# ADF_Copy_v0_5.net
KiCad netlist of a schematic drawn in EAGLE
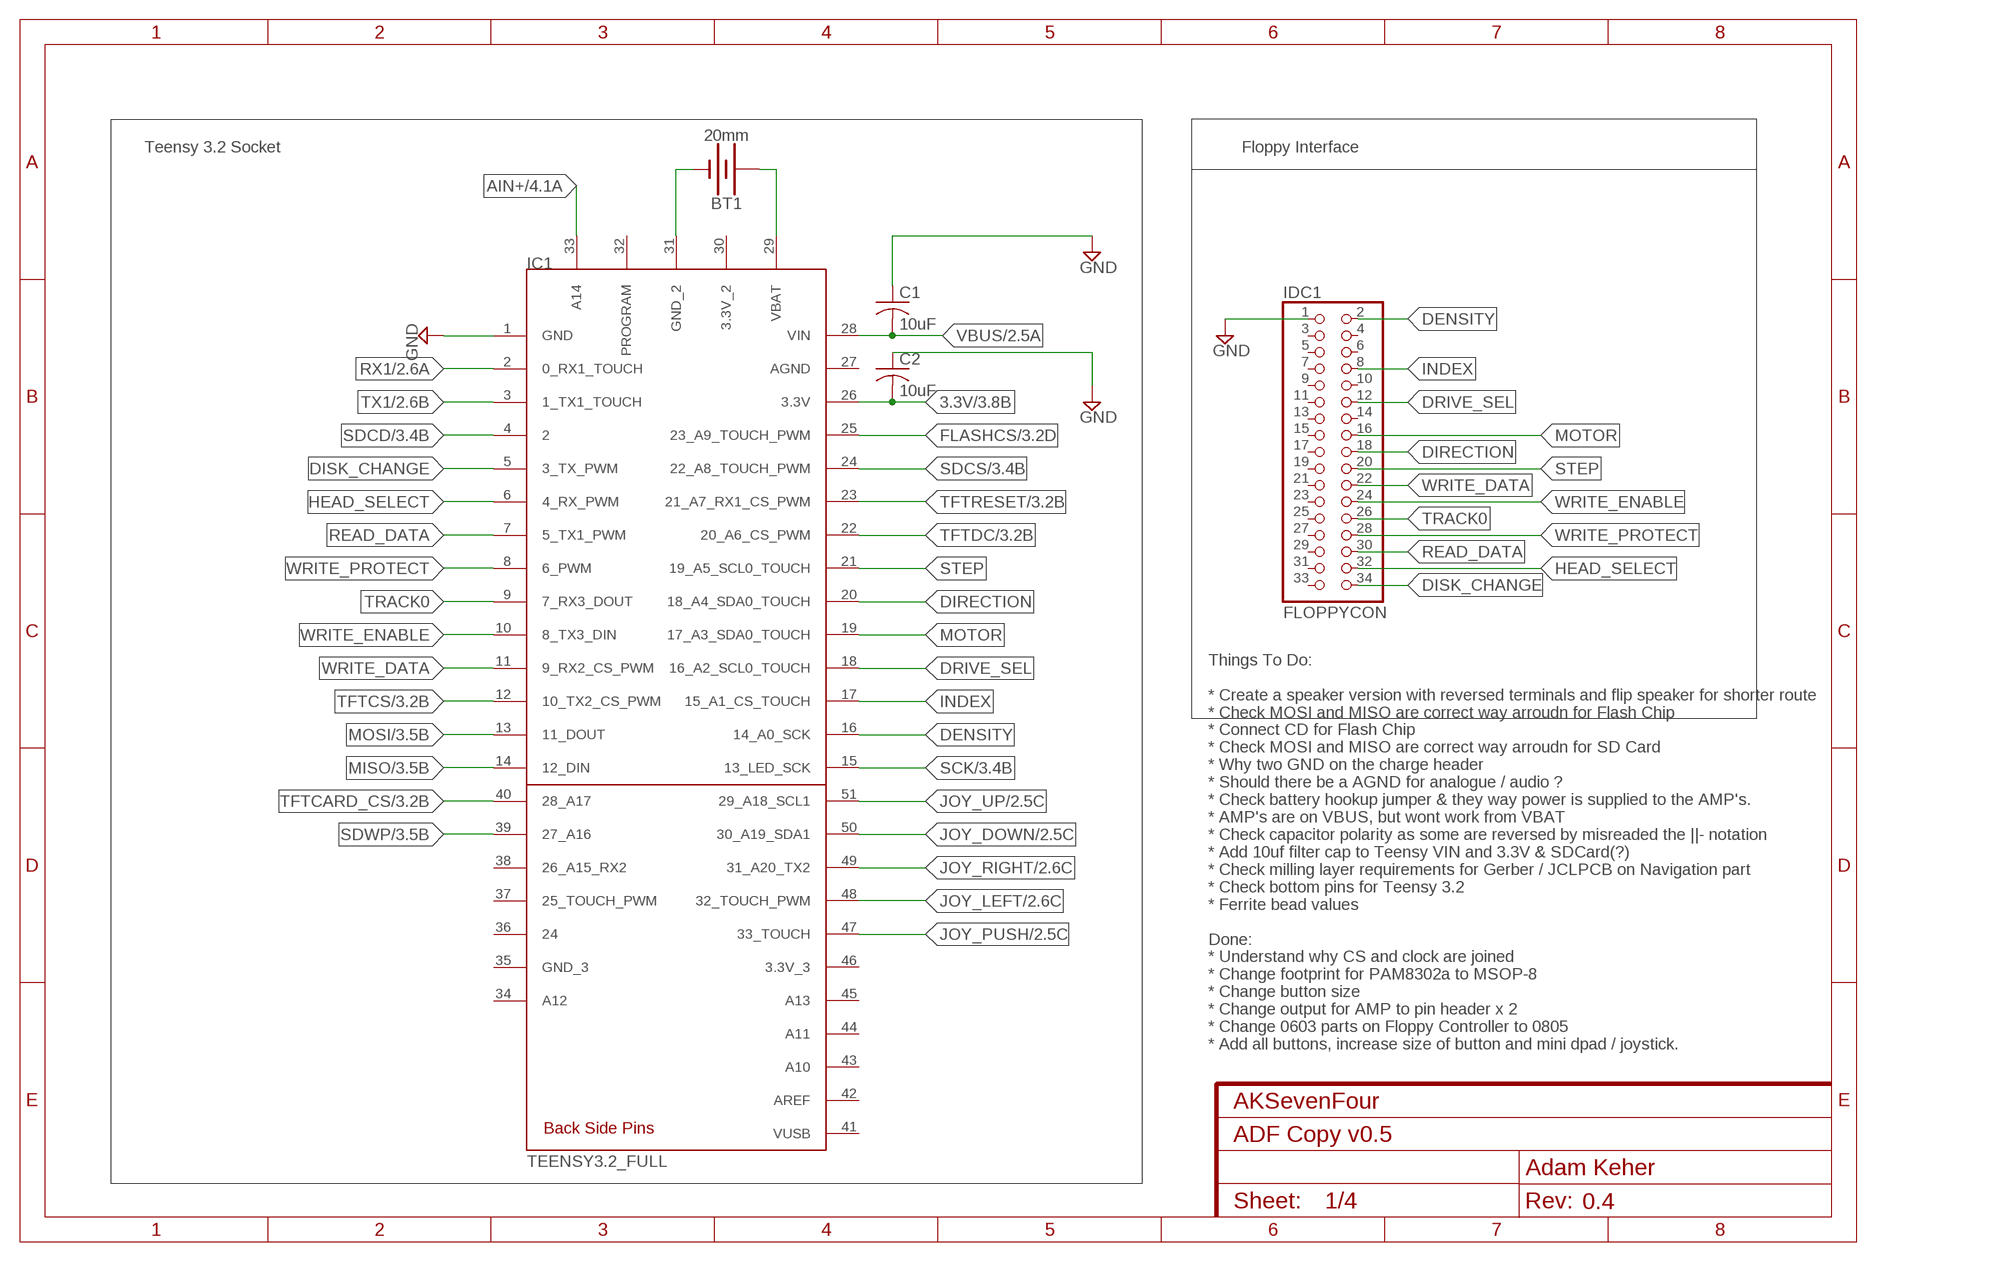
[diagram p0: schematic, sheet 1]
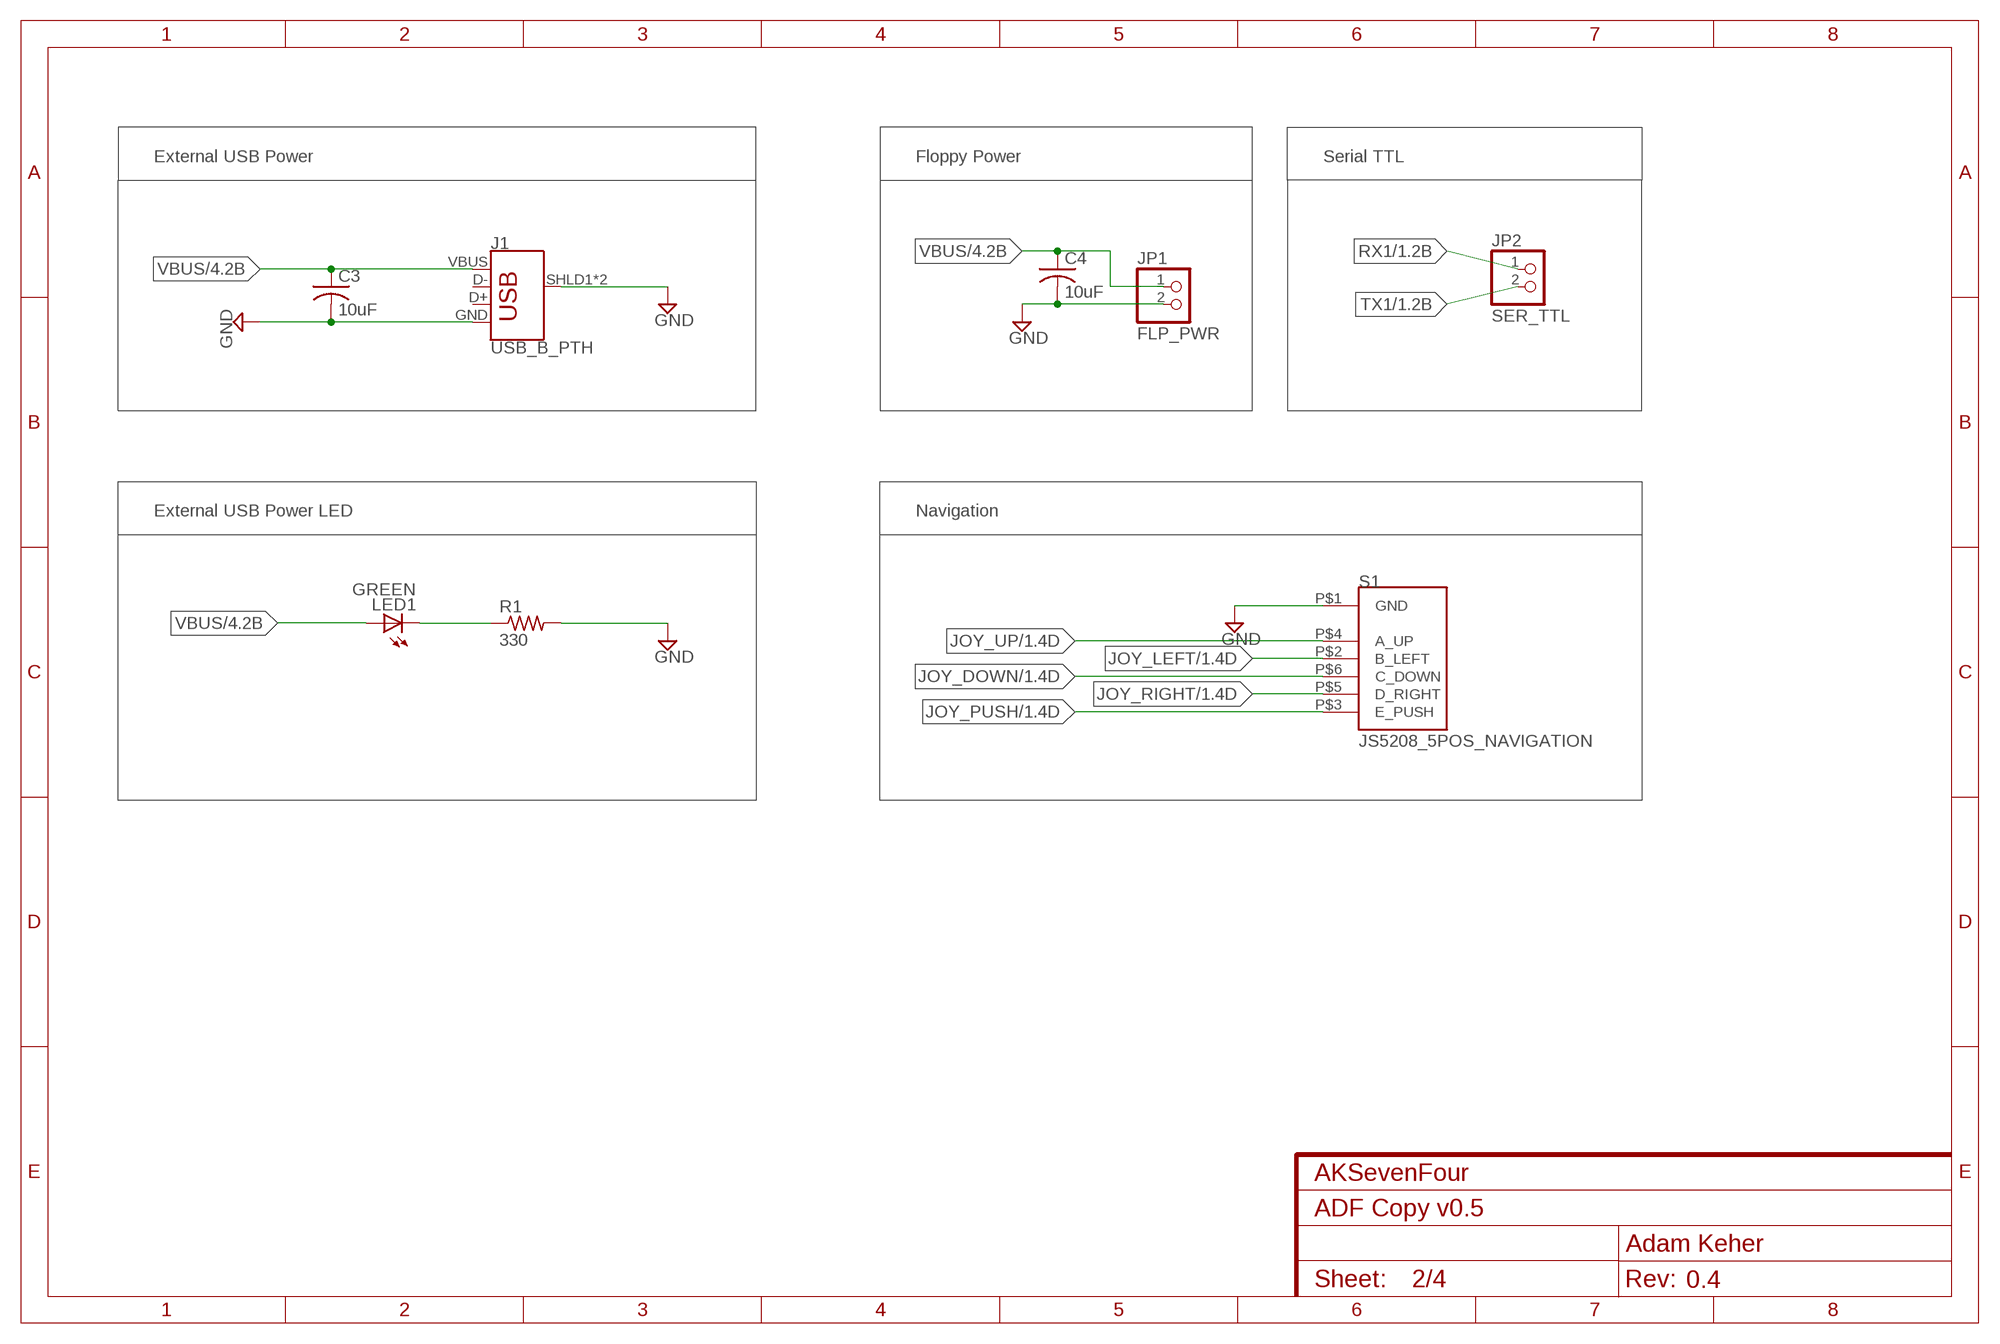
[diagram p1: schematic, sheet 2]
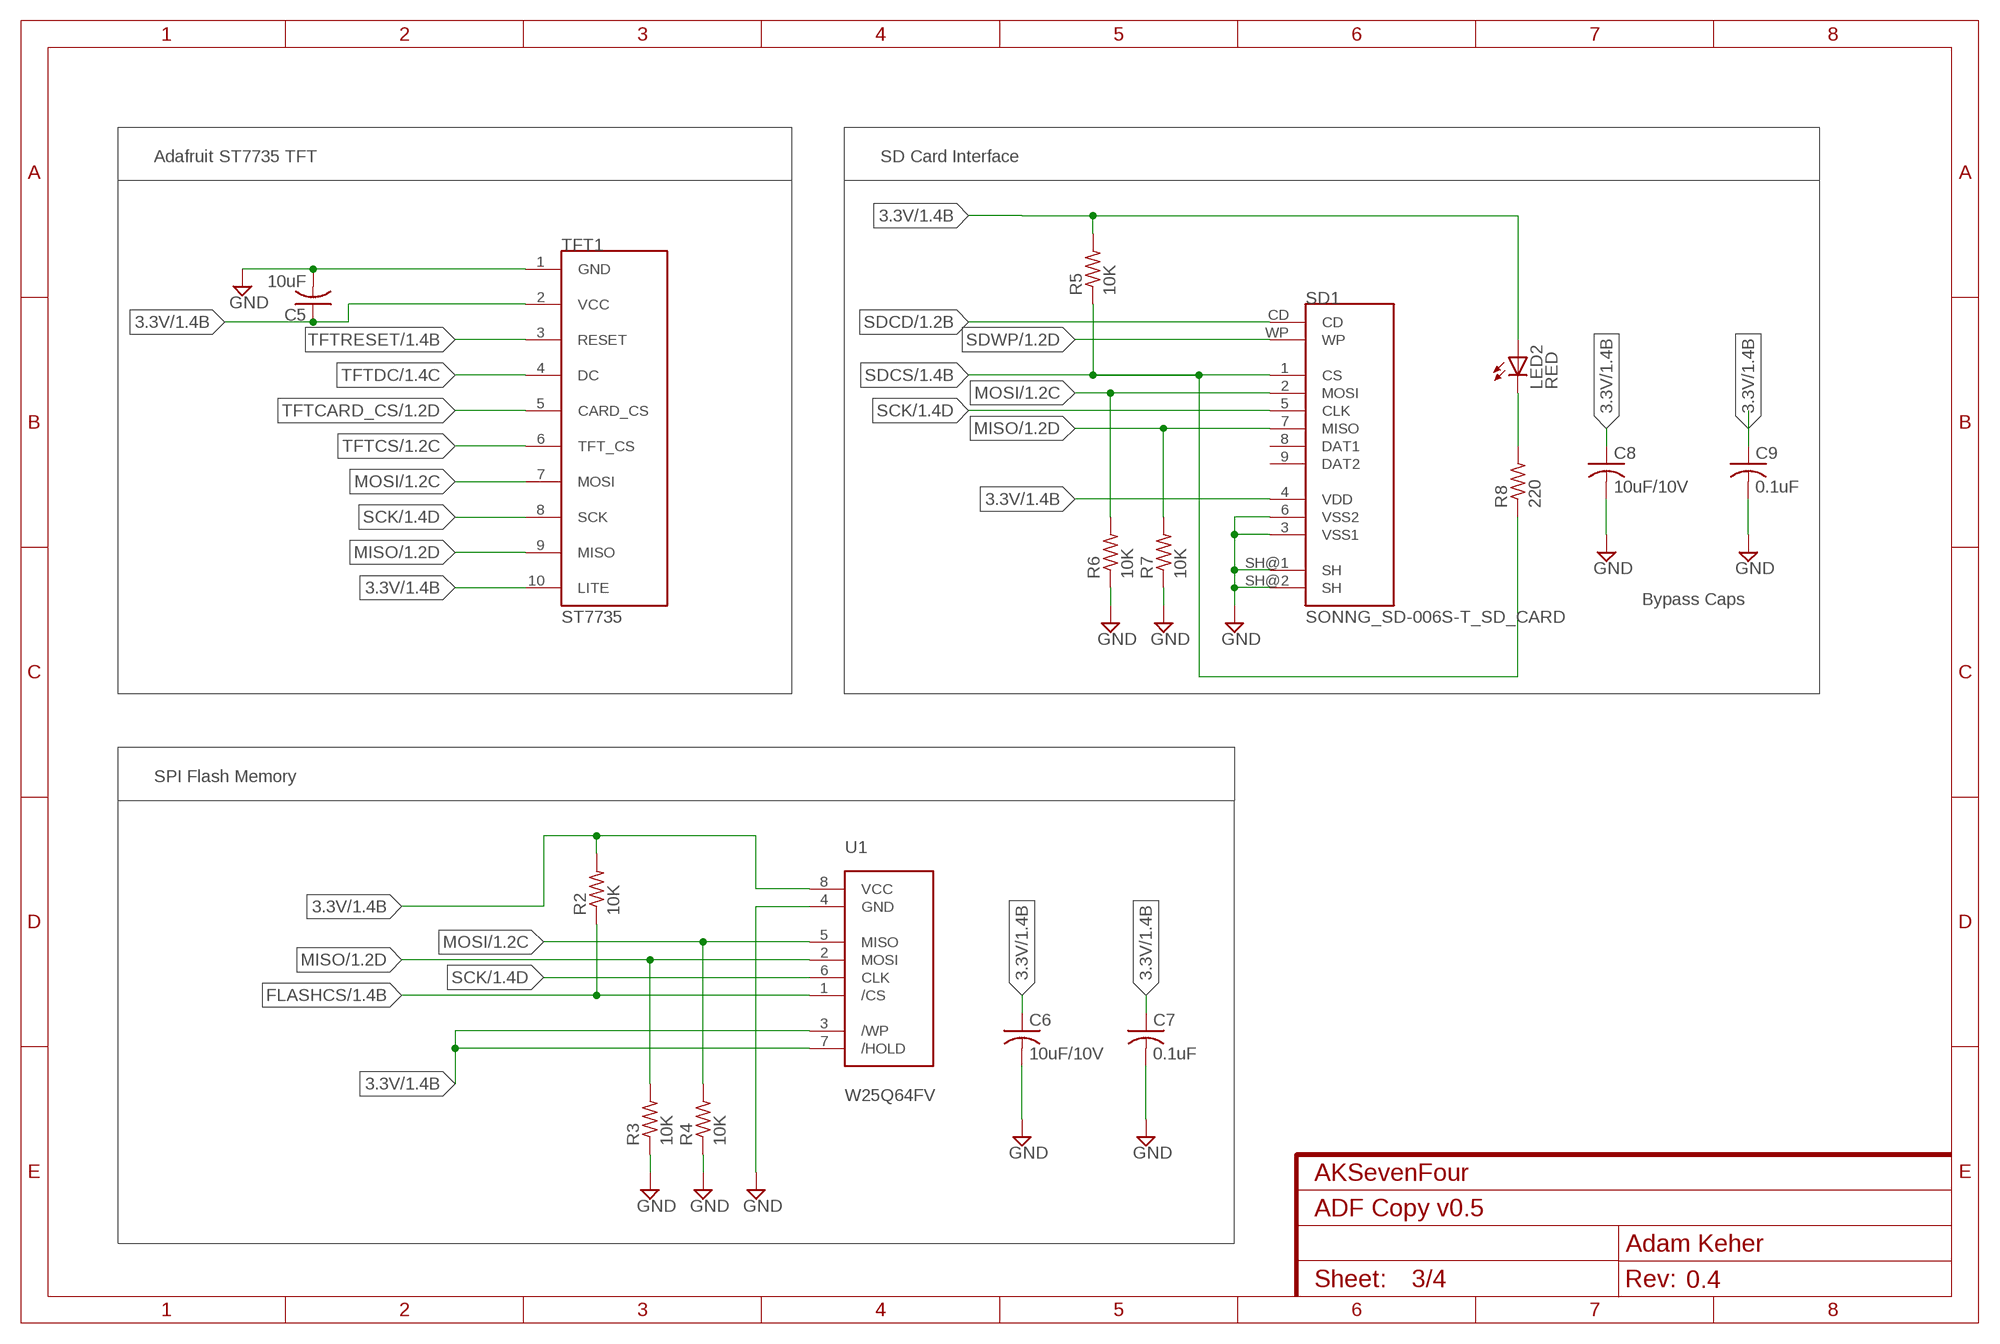
[diagram p2: schematic, sheet 3]
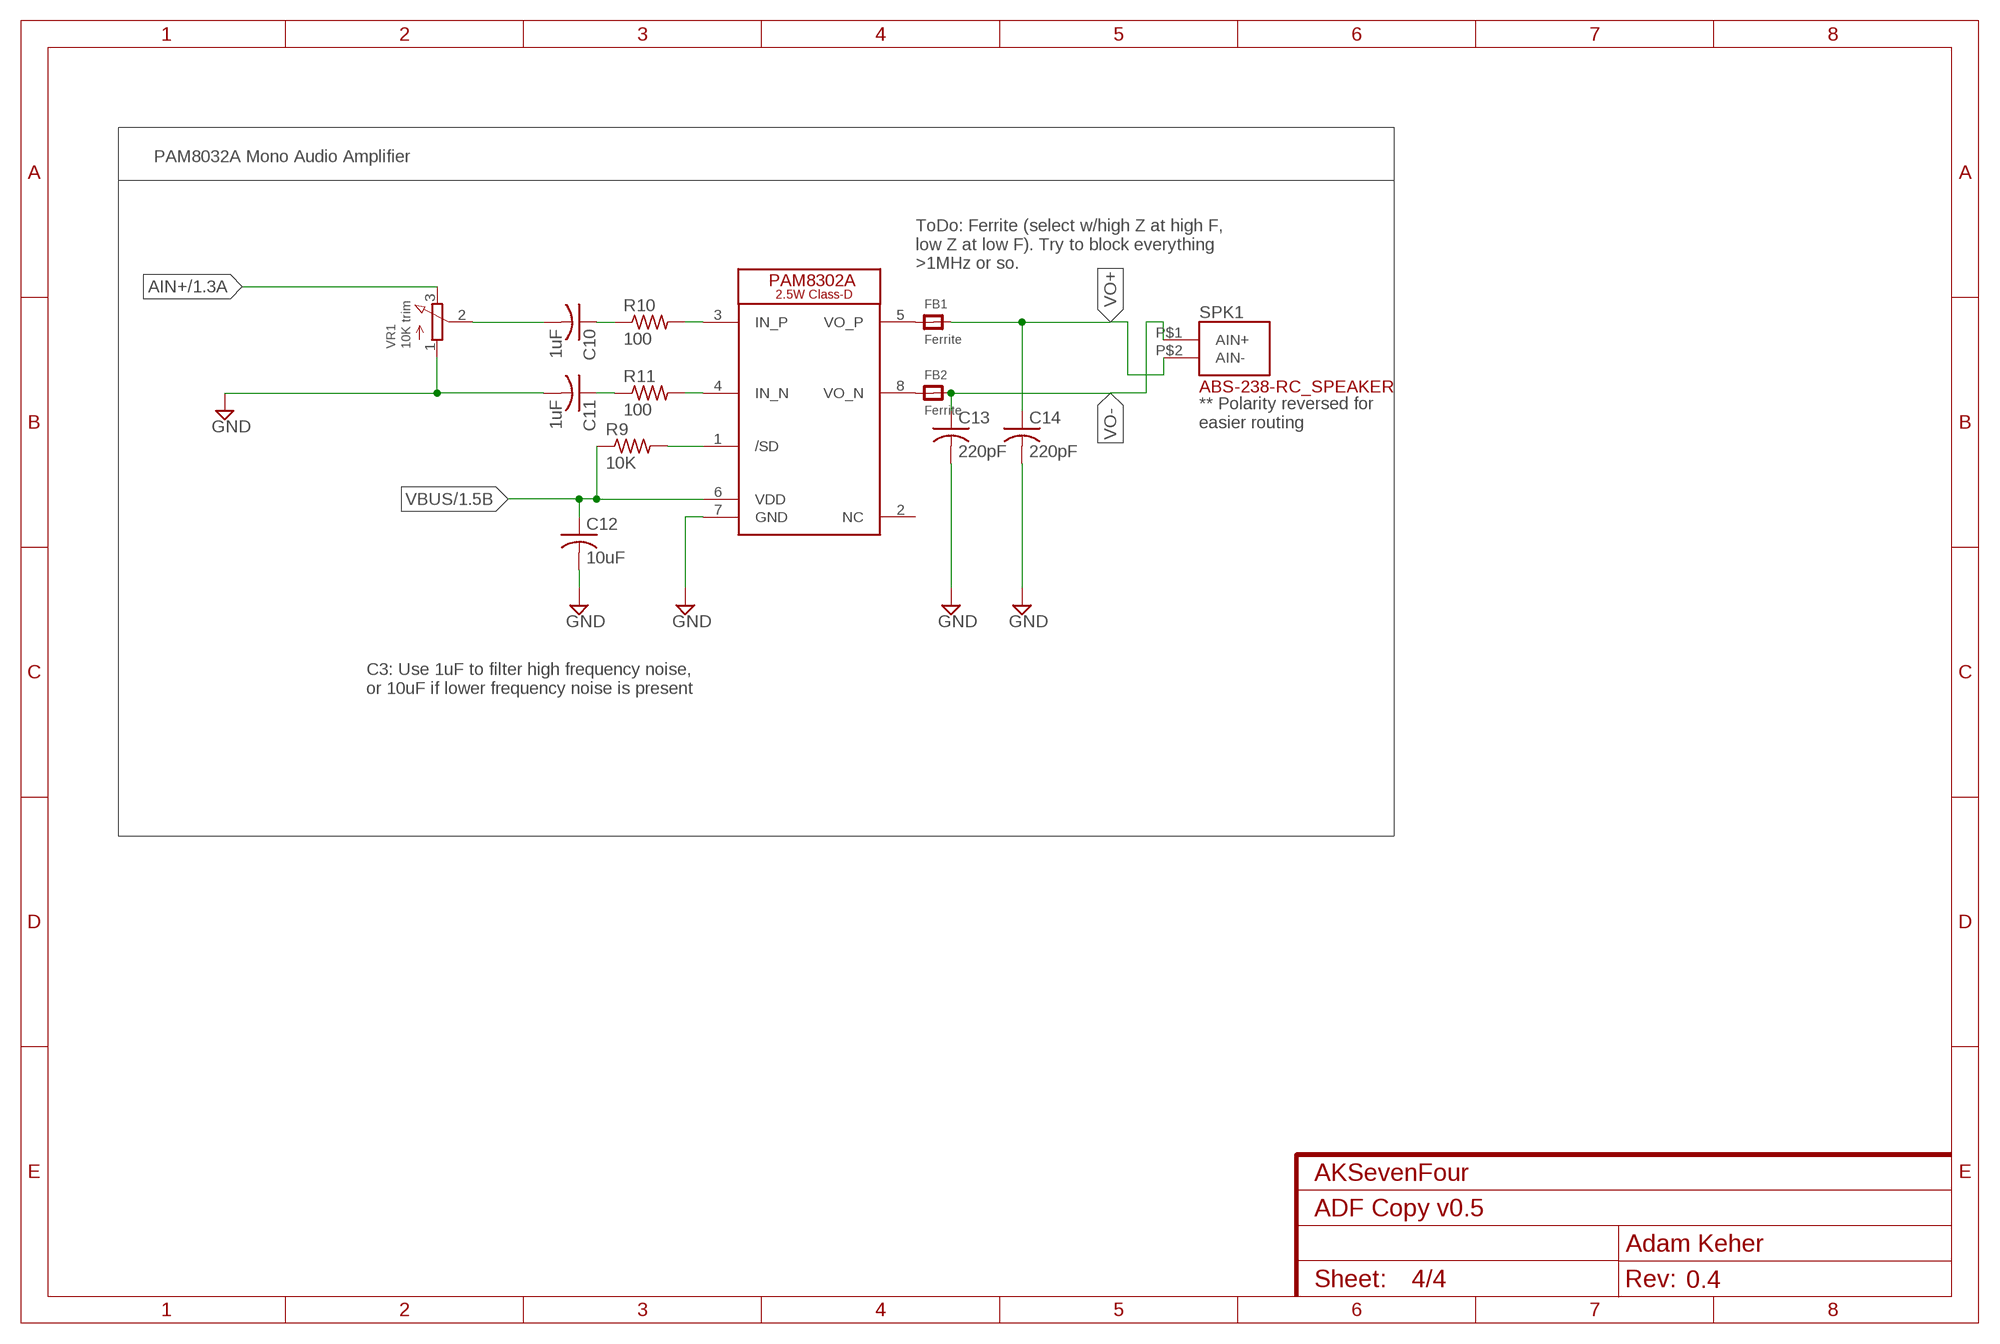
[diagram p3: schematic, sheet 4]

(export (version "E")
  (design (tool "Eeschema 10.0.6"))
  (components
    (comp (ref "C5")
      (value "10uF")
      (footprint "eagle-import:C0805")
      (libsource (lib "eagle-import") (part "C-USC0805"))
    )
    (comp (ref "C6")
      (value "10uF/10V")
      (footprint "eagle-import:C0805")
      (libsource (lib "eagle-import") (part "C-USC0805"))
    )
    (comp (ref "C7")
      (value "0.1uF")
      (footprint "eagle-import:C0805")
      (libsource (lib "eagle-import") (part "C-USC0805"))
    )
    (comp (ref "C8")
      (value "10uF/10V")
      (footprint "eagle-import:C0805")
      (libsource (lib "eagle-import") (part "C-USC0805"))
    )
    (comp (ref "C9")
      (value "0.1uF")
      (footprint "eagle-import:C0805")
      (libsource (lib "eagle-import") (part "C-USC0805"))
    )
    (comp (ref "LED2")
      (value "RED")
      (footprint "eagle-import:CHIP-LED0805")
      (libsource (lib "eagle-import") (part "LEDCHIP-LED0805"))
    )
    (comp (ref "R2")
      (value "10K")
      (footprint "eagle-import:R0805")
      (libsource (lib "eagle-import") (part "R-US_R0805"))
    )
    (comp (ref "R3")
      (value "10K")
      (footprint "eagle-import:R0805")
      (libsource (lib "eagle-import") (part "R-US_R0805"))
    )
    (comp (ref "R4")
      (value "10K")
      (footprint "eagle-import:R0805")
      (libsource (lib "eagle-import") (part "R-US_R0805"))
    )
    (comp (ref "R5")
      (value "10K")
      (footprint "eagle-import:R0805")
      (libsource (lib "eagle-import") (part "R-US_R0805"))
    )
    (comp (ref "R6")
      (value "10K")
      (footprint "eagle-import:R0805")
      (libsource (lib "eagle-import") (part "R-US_R0805"))
    )
    (comp (ref "R7")
      (value "10K")
      (footprint "eagle-import:R0805")
      (libsource (lib "eagle-import") (part "R-US_R0805"))
    )
    (comp (ref "R8")
      (value "220")
      (footprint "eagle-import:R0805")
      (libsource (lib "eagle-import") (part "R-US_R0805"))
    )
    (comp (ref "SD1")
      (value "SONNG_SD-006S-T_SD_CARD")
      (footprint "eagle-import:SD-006S-T")
      (libsource (lib "eagle-import") (part "SONNG_SD-006S-T_SD_CARD"))
    )
    (comp (ref "TFT1")
      (value "ST7735")
      (footprint "eagle-import:ST7735")
      (libsource (lib "eagle-import") (part "ST7735"))
    )
    (comp (ref "U1")
      (value "W25Q64FV")
      (footprint "eagle-import:SOIC8")
      (libsource (lib "eagle-import") (part "W25Q64FV"))
    )
    (comp (ref "BT1")
      (value "20mm")
      (footprint "eagle-import:BATTCOM_20MM_PTH")
      (libsource (lib "eagle-import") (part "BATTERY-20MM_PTH"))
    )
    (comp (ref "C1")
      (value "10uF")
      (footprint "eagle-import:C0805")
      (libsource (lib "eagle-import") (part "C-USC0805"))
    )
    (comp (ref "C2")
      (value "10uF")
      (footprint "eagle-import:C0805")
      (libsource (lib "eagle-import") (part "C-USC0805"))
    )
    (comp (ref "IC1")
      (value "TEENSY3.2_FULL")
      (footprint "eagle-import:DIP28X4-2.54-34.7X15.24MM")
      (libsource (lib "eagle-import") (part "TEENSY3.2_FULL"))
    )
    (comp (ref "IDC1")
      (value "FLOPPYCON")
      (footprint "eagle-import:2X17_90")
      (libsource (lib "eagle-import") (part "FLOPPYCON"))
    )
    (comp (ref "C10")
      (value "1uF")
      (footprint "eagle-import:C0805")
      (libsource (lib "eagle-import") (part "C-USC0805"))
    )
    (comp (ref "C11")
      (value "1uF")
      (footprint "eagle-import:C0805")
      (libsource (lib "eagle-import") (part "C-USC0805"))
    )
    (comp (ref "C12")
      (value "10uF")
      (footprint "eagle-import:C0805")
      (libsource (lib "eagle-import") (part "C-USC0805"))
    )
    (comp (ref "C13")
      (value "220pF")
      (footprint "eagle-import:C0805")
      (libsource (lib "eagle-import") (part "C-USC0805"))
    )
    (comp (ref "C14")
      (value "220pF")
      (footprint "eagle-import:C0805")
      (libsource (lib "eagle-import") (part "C-USC0805"))
    )
    (comp (ref "FB1")
      (value "Ferrite")
      (footprint "eagle-import:_0805")
      (libsource (lib "eagle-import") (part "FERRITE_0805"))
    )
    (comp (ref "FB2")
      (value "Ferrite")
      (footprint "eagle-import:_0805")
      (libsource (lib "eagle-import") (part "FERRITE_0805"))
    )
    (comp (ref "IC2")
      (value "PAM8302A")
      (footprint "eagle-import:SOIC8")
      (libsource (lib "eagle-import") (part "PAM8302A"))
    )
    (comp (ref "R9")
      (value "10K")
      (footprint "eagle-import:R0805")
      (libsource (lib "eagle-import") (part "R-US_R0805"))
    )
    (comp (ref "R10")
      (value "100")
      (footprint "eagle-import:R0805")
      (libsource (lib "eagle-import") (part "R-US_R0805"))
    )
    (comp (ref "R11")
      (value "100")
      (footprint "eagle-import:R0805")
      (libsource (lib "eagle-import") (part "R-US_R0805"))
    )
    (comp (ref "SPK1")
      (value "ABS-238-RC_SPEAKER")
      (footprint "eagle-import:ABS-238-RC_SPEAKER")
      (libsource (lib "eagle-import") (part "ABS-238-RC_SPEAKER"))
    )
    (comp (ref "VR1")
      (value "10K trim")
      (footprint "eagle-import:TRIMPOT_BOURNS_3303W")
      (libsource (lib "eagle-import") (part "TRIMPOT3303W/X"))
    )
    (comp (ref "C3")
      (value "10uF")
      (footprint "eagle-import:C0805")
      (libsource (lib "eagle-import") (part "C-USC0805"))
    )
    (comp (ref "C4")
      (value "10uF")
      (footprint "eagle-import:C0805")
      (libsource (lib "eagle-import") (part "C-USC0805"))
    )
    (comp (ref "J1")
      (value "USB_B_PTH")
      (footprint "eagle-import:USB-B-PTH")
      (libsource (lib "eagle-import") (part "USB_B_PTH"))
    )
    (comp (ref "JP1")
      (value "FLP_PWR")
      (footprint "eagle-import:1X02")
      (libsource (lib "eagle-import") (part "PINHD-1X2"))
    )
    (comp (ref "JP2")
      (value "SER_TTL")
      (footprint "eagle-import:1X02")
      (libsource (lib "eagle-import") (part "PINHD-1X2"))
    )
    (comp (ref "LED1")
      (value "GREEN")
      (footprint "eagle-import:CHIP-LED0805")
      (libsource (lib "eagle-import") (part "LEDCHIP-LED0805"))
    )
    (comp (ref "R1")
      (value "330")
      (footprint "eagle-import:R0805")
      (libsource (lib "eagle-import") (part "R-US_R0805"))
    )
    (comp (ref "S1")
      (value "JS5208_5POS_NAVIGATION")
      (footprint "eagle-import:JS5208_5POS_NAVIGATION")
      (libsource (lib "eagle-import") (part "JS5208_5POS_NAVIGATION"))
    )
  )
  (nets
    (net (code "1") (name "3.3V") (class "Default")
      (node (ref "C2") (pin "2") (pinfunction "2_2") (pintype "passive"))
      (node (ref "C5") (pin "1") (pinfunction "1_1") (pintype "passive"))
      (node (ref "C6") (pin "1") (pinfunction "1_1") (pintype "passive"))
      (node (ref "C7") (pin "1") (pinfunction "1_1") (pintype "passive"))
      (node (ref "C8") (pin "1") (pinfunction "1_1") (pintype "passive"))
      (node (ref "C9") (pin "1") (pinfunction "1_1") (pintype "passive"))
      (node (ref "IC1") (pin "26") (pinfunction "3.3V_26") (pintype "bidirectional"))
      (node (ref "LED2") (pin "A") (pinfunction "A_A") (pintype "passive"))
      (node (ref "R2") (pin "2") (pinfunction "2_2") (pintype "passive"))
      (node (ref "R5") (pin "2") (pinfunction "2_2") (pintype "passive"))
      (node (ref "SD1") (pin "4") (pinfunction "VDD_4") (pintype "bidirectional"))
      (node (ref "TFT1") (pin "10") (pinfunction "LITE_10") (pintype "bidirectional"))
      (node (ref "TFT1") (pin "2") (pinfunction "VCC_2") (pintype "bidirectional"))
      (node (ref "U1") (pin "3") (pinfunction "/WP_3") (pintype "bidirectional"))
      (node (ref "U1") (pin "7") (pinfunction "/HOLD_7") (pintype "bidirectional"))
      (node (ref "U1") (pin "8") (pinfunction "VCC_8") (pintype "bidirectional"))
    )
    (net (code "2") (name "AIN+") (class "Default")
      (node (ref "IC1") (pin "33") (pinfunction "A14_33") (pintype "bidirectional"))
      (node (ref "VR1") (pin "3") (pinfunction "E_3") (pintype "passive"))
    )
    (net (code "3") (name "DENSITY") (class "Default")
      (node (ref "IC1") (pin "16") (pinfunction "14_A0_SCK_16") (pintype "bidirectional"))
      (node (ref "IDC1") (pin "2") (pinfunction "2_2") (pintype "passive"))
    )
    (net (code "4") (name "DIRECTION") (class "Default")
      (node (ref "IC1") (pin "20") (pinfunction "18_A4_SDA0_TOUCH_20") (pintype "bidirectional"))
      (node (ref "IDC1") (pin "18") (pinfunction "18_18") (pintype "passive"))
    )
    (net (code "5") (name "DISK_CHANGE") (class "Default")
      (node (ref "IC1") (pin "5") (pinfunction "3_TX_PWM_5") (pintype "bidirectional"))
      (node (ref "IDC1") (pin "34") (pinfunction "34_34") (pintype "passive"))
    )
    (net (code "6") (name "DRIVE_SEL") (class "Default")
      (node (ref "IC1") (pin "18") (pinfunction "16_A2_SCL0_TOUCH_18") (pintype "bidirectional"))
      (node (ref "IDC1") (pin "12") (pinfunction "12_12") (pintype "passive"))
    )
    (net (code "7") (name "FLASHCS") (class "Default")
      (node (ref "IC1") (pin "25") (pinfunction "23_A9_TOUCH_PWM_25") (pintype "bidirectional"))
      (node (ref "R2") (pin "1") (pinfunction "1_1") (pintype "passive"))
      (node (ref "U1") (pin "1") (pinfunction "/CS_1") (pintype "bidirectional"))
    )
    (net (code "8") (name "GND") (class "Default")
      (node (ref "C1") (pin "1") (pinfunction "1_1") (pintype "passive"))
      (node (ref "C11") (pin "2") (pinfunction "2_2") (pintype "passive"))
      (node (ref "C12") (pin "2") (pinfunction "2_2") (pintype "passive"))
      (node (ref "C13") (pin "2") (pinfunction "2_2") (pintype "passive"))
      (node (ref "C14") (pin "2") (pinfunction "2_2") (pintype "passive"))
      (node (ref "C2") (pin "1") (pinfunction "1_1") (pintype "passive"))
      (node (ref "C3") (pin "2") (pinfunction "2_2") (pintype "passive"))
      (node (ref "C4") (pin "2") (pinfunction "2_2") (pintype "passive"))
      (node (ref "C5") (pin "2") (pinfunction "2_2") (pintype "passive"))
      (node (ref "C6") (pin "2") (pinfunction "2_2") (pintype "passive"))
      (node (ref "C7") (pin "2") (pinfunction "2_2") (pintype "passive"))
      (node (ref "C8") (pin "2") (pinfunction "2_2") (pintype "passive"))
      (node (ref "C9") (pin "2") (pinfunction "2_2") (pintype "passive"))
      (node (ref "IC1") (pin "1") (pinfunction "GND_1") (pintype "bidirectional"))
      (node (ref "IC2") (pin "7") (pinfunction "GND_7") (pintype "bidirectional"))
      (node (ref "IDC1") (pin "1") (pinfunction "1_1") (pintype "passive"))
      (node (ref "J1") (pin "GND") (pinfunction "GND_GND") (pintype "power_in"))
      (node (ref "J1") (pin "SHLD1") (pinfunction "SHIELD_SHLD1") (pintype "bidirectional"))
      (node (ref "J1") (pin "SHLD2") (pinfunction "SHIELD_SHLD2") (pintype "bidirectional"))
      (node (ref "JP1") (pin "2") (pinfunction "2_2") (pintype "passive"))
      (node (ref "R1") (pin "2") (pinfunction "2_2") (pintype "passive"))
      (node (ref "R3") (pin "1") (pinfunction "1_1") (pintype "passive"))
      (node (ref "R4") (pin "1") (pinfunction "1_1") (pintype "passive"))
      (node (ref "R6") (pin "1") (pinfunction "1_1") (pintype "passive"))
      (node (ref "R7") (pin "1") (pinfunction "1_1") (pintype "passive"))
      (node (ref "S1") (pin "P$1") (pinfunction "GND_P$1") (pintype "bidirectional"))
      (node (ref "SD1") (pin "3") (pinfunction "VSS1_3") (pintype "bidirectional"))
      (node (ref "SD1") (pin "6") (pinfunction "VSS2_6") (pintype "bidirectional"))
      (node (ref "SD1") (pin "SH@1") (pinfunction "SH_SH@1") (pintype "bidirectional"))
      (node (ref "SD1") (pin "SH@2") (pinfunction "SH_SH@2") (pintype "bidirectional"))
      (node (ref "TFT1") (pin "1") (pinfunction "GND_1") (pintype "bidirectional"))
      (node (ref "U1") (pin "4") (pinfunction "GND_4") (pintype "bidirectional"))
      (node (ref "VR1") (pin "1") (pinfunction "A_1") (pintype "passive"))
    )
    (net (code "9") (name "HEAD_SELECT") (class "Default")
      (node (ref "IC1") (pin "6") (pinfunction "4_RX_PWM_6") (pintype "bidirectional"))
      (node (ref "IDC1") (pin "32") (pinfunction "32_32") (pintype "passive"))
    )
    (net (code "10") (name "INDEX") (class "Default")
      (node (ref "IC1") (pin "17") (pinfunction "15_A1_CS_TOUCH_17") (pintype "bidirectional"))
      (node (ref "IDC1") (pin "8") (pinfunction "8_8") (pintype "passive"))
    )
    (net (code "11") (name "JOY_DOWN") (class "Default")
      (node (ref "IC1") (pin "50") (pinfunction "30_A19_SDA1_50") (pintype "bidirectional"))
      (node (ref "S1") (pin "P$6") (pinfunction "C_DOWN_P$6") (pintype "bidirectional"))
    )
    (net (code "12") (name "JOY_LEFT") (class "Default")
      (node (ref "IC1") (pin "48") (pinfunction "32_TOUCH_PWM_48") (pintype "bidirectional"))
      (node (ref "S1") (pin "P$2") (pinfunction "B_LEFT_P$2") (pintype "bidirectional"))
    )
    (net (code "13") (name "JOY_PUSH") (class "Default")
      (node (ref "IC1") (pin "47") (pinfunction "33_TOUCH_47") (pintype "bidirectional"))
      (node (ref "S1") (pin "P$3") (pinfunction "E_PUSH_P$3") (pintype "bidirectional"))
    )
    (net (code "14") (name "JOY_RIGHT") (class "Default")
      (node (ref "IC1") (pin "49") (pinfunction "31_A20_TX2_49") (pintype "bidirectional"))
      (node (ref "S1") (pin "P$5") (pinfunction "D_RIGHT_P$5") (pintype "bidirectional"))
    )
    (net (code "15") (name "JOY_UP") (class "Default")
      (node (ref "IC1") (pin "51") (pinfunction "29_A18_SCL1_51") (pintype "bidirectional"))
      (node (ref "S1") (pin "P$4") (pinfunction "A_UP_P$4") (pintype "bidirectional"))
    )
    (net (code "16") (name "MISO") (class "Default")
      (node (ref "IC1") (pin "14") (pinfunction "12_DIN_14") (pintype "bidirectional"))
      (node (ref "R3") (pin "2") (pinfunction "2_2") (pintype "passive"))
      (node (ref "R7") (pin "2") (pinfunction "2_2") (pintype "passive"))
      (node (ref "SD1") (pin "7") (pinfunction "MISO_7") (pintype "bidirectional"))
      (node (ref "TFT1") (pin "9") (pinfunction "MISO_9") (pintype "bidirectional"))
      (node (ref "U1") (pin "2") (pinfunction "MOSI_2") (pintype "bidirectional"))
    )
    (net (code "17") (name "MOSI") (class "Default")
      (node (ref "IC1") (pin "13") (pinfunction "11_DOUT_13") (pintype "bidirectional"))
      (node (ref "R4") (pin "2") (pinfunction "2_2") (pintype "passive"))
      (node (ref "R6") (pin "2") (pinfunction "2_2") (pintype "passive"))
      (node (ref "SD1") (pin "2") (pinfunction "MOSI_2") (pintype "bidirectional"))
      (node (ref "TFT1") (pin "7") (pinfunction "MOSI_7") (pintype "bidirectional"))
      (node (ref "U1") (pin "5") (pinfunction "MISO_5") (pintype "bidirectional"))
    )
    (net (code "18") (name "MOTOR") (class "Default")
      (node (ref "IC1") (pin "19") (pinfunction "17_A3_SDA0_TOUCH_19") (pintype "bidirectional"))
      (node (ref "IDC1") (pin "16") (pinfunction "16_16") (pintype "passive"))
    )
    (net (code "19") (name "Net-(BT1-+)") (class "Default")
      (node (ref "BT1") (pin "1") (pinfunction "+_1") (pintype "power_in"))
      (node (ref "IC1") (pin "29") (pinfunction "VBAT_29") (pintype "bidirectional"))
    )
    (net (code "20") (name "Net-(BT1--)") (class "Default")
      (node (ref "BT1") (pin "2") (pinfunction "-_2") (pintype "power_in"))
      (node (ref "IC1") (pin "31") (pinfunction "GND_2_31") (pintype "bidirectional"))
    )
    (net (code "21") (name "Net-(C10-Pad1)") (class "Default")
      (node (ref "C10") (pin "1") (pinfunction "1_1") (pintype "passive"))
      (node (ref "R10") (pin "1") (pinfunction "1_1") (pintype "passive"))
    )
    (net (code "22") (name "Net-(C11-Pad1)") (class "Default")
      (node (ref "C11") (pin "1") (pinfunction "1_1") (pintype "passive"))
      (node (ref "R11") (pin "1") (pinfunction "1_1") (pintype "passive"))
    )
    (net (code "23") (name "Net-(FB1-P$1)") (class "Default")
      (node (ref "FB1") (pin "1") (pinfunction "P$1_1") (pintype "passive"))
      (node (ref "IC2") (pin "5") (pinfunction "VO_P_5") (pintype "bidirectional"))
    )
    (net (code "24") (name "Net-(FB2-P$1)") (class "Default")
      (node (ref "FB2") (pin "1") (pinfunction "P$1_1") (pintype "passive"))
      (node (ref "IC2") (pin "8") (pinfunction "VO_N_8") (pintype "bidirectional"))
    )
    (net (code "25") (name "Net-(IC2-IN_N)") (class "Default")
      (node (ref "IC2") (pin "4") (pinfunction "IN_N_4") (pintype "bidirectional"))
      (node (ref "R11") (pin "2") (pinfunction "2_2") (pintype "passive"))
    )
    (net (code "26") (name "Net-(IC2-IN_P)") (class "Default")
      (node (ref "IC2") (pin "3") (pinfunction "IN_P_3") (pintype "bidirectional"))
      (node (ref "R10") (pin "2") (pinfunction "2_2") (pintype "passive"))
    )
    (net (code "27") (name "Net-(IC2-{slash}SD)") (class "Default")
      (node (ref "IC2") (pin "1") (pinfunction "/SD_1") (pintype "bidirectional"))
      (node (ref "R9") (pin "2") (pinfunction "2_2") (pintype "passive"))
    )
    (net (code "28") (name "Net-(LED1-PadC)") (class "Default")
      (node (ref "LED1") (pin "C") (pinfunction "C_C") (pintype "passive"))
      (node (ref "R1") (pin "1") (pinfunction "1_1") (pintype "passive"))
    )
    (net (code "29") (name "Net-(LED2-PadC)") (class "Default")
      (node (ref "LED2") (pin "C") (pinfunction "C_C") (pintype "passive"))
      (node (ref "R8") (pin "2") (pinfunction "2_2") (pintype "passive"))
    )
    (net (code "30") (name "Net-(VR1-S)") (class "Default")
      (node (ref "C10") (pin "2") (pinfunction "2_2") (pintype "passive"))
      (node (ref "VR1") (pin "2") (pinfunction "S_2") (pintype "passive"))
    )
    (net (code "31") (name "READ_DATA") (class "Default")
      (node (ref "IC1") (pin "7") (pinfunction "5_TX1_PWM_7") (pintype "bidirectional"))
      (node (ref "IDC1") (pin "30") (pinfunction "30_30") (pintype "passive"))
    )
    (net (code "32") (name "RX1") (class "Default")
      (node (ref "IC1") (pin "2") (pinfunction "0_RX1_TOUCH_2") (pintype "bidirectional"))
      (node (ref "JP2") (pin "1") (pinfunction "1_1") (pintype "passive"))
    )
    (net (code "33") (name "SCK") (class "Default")
      (node (ref "IC1") (pin "15") (pinfunction "13_LED_SCK_15") (pintype "bidirectional"))
      (node (ref "SD1") (pin "5") (pinfunction "CLK_5") (pintype "bidirectional"))
      (node (ref "TFT1") (pin "8") (pinfunction "SCK_8") (pintype "bidirectional"))
      (node (ref "U1") (pin "6") (pinfunction "CLK_6") (pintype "bidirectional"))
    )
    (net (code "34") (name "SDCD") (class "Default")
      (node (ref "IC1") (pin "4") (pinfunction "2_4") (pintype "bidirectional"))
      (node (ref "SD1") (pin "CD") (pinfunction "CD_CD") (pintype "bidirectional"))
    )
    (net (code "35") (name "SDCS") (class "Default")
      (node (ref "IC1") (pin "24") (pinfunction "22_A8_TOUCH_PWM_24") (pintype "bidirectional"))
      (node (ref "R5") (pin "1") (pinfunction "1_1") (pintype "passive"))
      (node (ref "R8") (pin "1") (pinfunction "1_1") (pintype "passive"))
      (node (ref "SD1") (pin "1") (pinfunction "CS_1") (pintype "bidirectional"))
    )
    (net (code "36") (name "SDWP") (class "Default")
      (node (ref "IC1") (pin "39") (pinfunction "27_A16_39") (pintype "bidirectional"))
      (node (ref "SD1") (pin "WP") (pinfunction "WP_WP") (pintype "bidirectional"))
    )
    (net (code "37") (name "STEP") (class "Default")
      (node (ref "IC1") (pin "21") (pinfunction "19_A5_SCL0_TOUCH_21") (pintype "bidirectional"))
      (node (ref "IDC1") (pin "20") (pinfunction "20_20") (pintype "passive"))
    )
    (net (code "38") (name "TFTCARD_CS") (class "Default")
      (node (ref "IC1") (pin "40") (pinfunction "28_A17_40") (pintype "bidirectional"))
      (node (ref "TFT1") (pin "5") (pinfunction "CARD_CS_5") (pintype "bidirectional"))
    )
    (net (code "39") (name "TFTCS") (class "Default")
      (node (ref "IC1") (pin "12") (pinfunction "10_TX2_CS_PWM_12") (pintype "bidirectional"))
      (node (ref "TFT1") (pin "6") (pinfunction "TFT_CS_6") (pintype "bidirectional"))
    )
    (net (code "40") (name "TFTDC") (class "Default")
      (node (ref "IC1") (pin "22") (pinfunction "20_A6_CS_PWM_22") (pintype "bidirectional"))
      (node (ref "TFT1") (pin "4") (pinfunction "DC_4") (pintype "bidirectional"))
    )
    (net (code "41") (name "TFTRESET") (class "Default")
      (node (ref "IC1") (pin "23") (pinfunction "21_A7_RX1_CS_PWM_23") (pintype "bidirectional"))
      (node (ref "TFT1") (pin "3") (pinfunction "RESET_3") (pintype "bidirectional"))
    )
    (net (code "42") (name "TRACK0") (class "Default")
      (node (ref "IC1") (pin "9") (pinfunction "7_RX3_DOUT_9") (pintype "bidirectional"))
      (node (ref "IDC1") (pin "26") (pinfunction "26_26") (pintype "passive"))
    )
    (net (code "43") (name "TX1") (class "Default")
      (node (ref "IC1") (pin "3") (pinfunction "1_TX1_TOUCH_3") (pintype "bidirectional"))
      (node (ref "JP2") (pin "2") (pinfunction "2_2") (pintype "passive"))
    )
    (net (code "44") (name "VBUS") (class "Default")
      (node (ref "C1") (pin "2") (pinfunction "2_2") (pintype "passive"))
      (node (ref "C12") (pin "1") (pinfunction "1_1") (pintype "passive"))
      (node (ref "C3") (pin "1") (pinfunction "1_1") (pintype "passive"))
      (node (ref "C4") (pin "1") (pinfunction "1_1") (pintype "passive"))
      (node (ref "IC1") (pin "28") (pinfunction "VIN_28") (pintype "bidirectional"))
      (node (ref "IC2") (pin "6") (pinfunction "VDD_6") (pintype "bidirectional"))
      (node (ref "J1") (pin "VBUS") (pinfunction "VBUS_VBUS") (pintype "power_in"))
      (node (ref "JP1") (pin "1") (pinfunction "1_1") (pintype "passive"))
      (node (ref "LED1") (pin "A") (pinfunction "A_A") (pintype "passive"))
      (node (ref "R9") (pin "1") (pinfunction "1_1") (pintype "passive"))
    )
    (net (code "45") (name "VO+") (class "Default")
      (node (ref "C14") (pin "1") (pinfunction "1_1") (pintype "passive"))
      (node (ref "FB1") (pin "2") (pinfunction "P$2_2") (pintype "passive"))
      (node (ref "SPK1") (pin "P$2") (pinfunction "AIN-_P$2") (pintype "bidirectional"))
    )
    (net (code "46") (name "VO-") (class "Default")
      (node (ref "C13") (pin "1") (pinfunction "1_1") (pintype "passive"))
      (node (ref "FB2") (pin "2") (pinfunction "P$2_2") (pintype "passive"))
      (node (ref "SPK1") (pin "P$1") (pinfunction "AIN+_P$1") (pintype "bidirectional"))
    )
    (net (code "47") (name "WRITE_DATA") (class "Default")
      (node (ref "IC1") (pin "11") (pinfunction "9_RX2_CS_PWM_11") (pintype "bidirectional"))
      (node (ref "IDC1") (pin "22") (pinfunction "22_22") (pintype "passive"))
    )
    (net (code "48") (name "WRITE_ENABLE") (class "Default")
      (node (ref "IC1") (pin "10") (pinfunction "8_TX3_DIN_10") (pintype "bidirectional"))
      (node (ref "IDC1") (pin "24") (pinfunction "24_24") (pintype "passive"))
    )
    (net (code "49") (name "WRITE_PROTECT") (class "Default")
      (node (ref "IC1") (pin "8") (pinfunction "6_PWM_8") (pintype "bidirectional"))
      (node (ref "IDC1") (pin "28") (pinfunction "28_28") (pintype "passive"))
    )
    (net (code "50") (name "unconnected-(IC1-3.3V_2-Pad30)") (class "Default")
      (node (ref "IC1") (pin "30") (pinfunction "3.3V_2_30") (pintype "bidirectional"))
    )
    (net (code "51") (name "unconnected-(IC1-3.3V_3-Pad46)") (class "Default")
      (node (ref "IC1") (pin "46") (pinfunction "3.3V_3_46") (pintype "bidirectional"))
    )
    (net (code "52") (name "unconnected-(IC1-24-Pad36)") (class "Default")
      (node (ref "IC1") (pin "36") (pinfunction "24_36") (pintype "bidirectional"))
    )
    (net (code "53") (name "unconnected-(IC1-25_TOUCH_PWM-Pad37)") (class "Default")
      (node (ref "IC1") (pin "37") (pinfunction "25_TOUCH_PWM_37") (pintype "bidirectional"))
    )
    (net (code "54") (name "unconnected-(IC1-26_A15_RX2-Pad38)") (class "Default")
      (node (ref "IC1") (pin "38") (pinfunction "26_A15_RX2_38") (pintype "bidirectional"))
    )
    (net (code "55") (name "unconnected-(IC1-A10-Pad43)") (class "Default")
      (node (ref "IC1") (pin "43") (pinfunction "A10_43") (pintype "bidirectional"))
    )
    (net (code "56") (name "unconnected-(IC1-A11-Pad44)") (class "Default")
      (node (ref "IC1") (pin "44") (pinfunction "A11_44") (pintype "bidirectional"))
    )
    (net (code "57") (name "unconnected-(IC1-A12-Pad34)") (class "Default")
      (node (ref "IC1") (pin "34") (pinfunction "A12_34") (pintype "bidirectional"))
    )
    (net (code "58") (name "unconnected-(IC1-A13-Pad45)") (class "Default")
      (node (ref "IC1") (pin "45") (pinfunction "A13_45") (pintype "bidirectional"))
    )
    (net (code "59") (name "unconnected-(IC1-AGND-Pad27)") (class "Default")
      (node (ref "IC1") (pin "27") (pinfunction "AGND_27") (pintype "bidirectional"))
    )
    (net (code "60") (name "unconnected-(IC1-AREF-Pad42)") (class "Default")
      (node (ref "IC1") (pin "42") (pinfunction "AREF_42") (pintype "bidirectional"))
    )
    (net (code "61") (name "unconnected-(IC1-GND_3-Pad35)") (class "Default")
      (node (ref "IC1") (pin "35") (pinfunction "GND_3_35") (pintype "bidirectional"))
    )
    (net (code "62") (name "unconnected-(IC1-PROGRAM-Pad32)") (class "Default")
      (node (ref "IC1") (pin "32") (pinfunction "PROGRAM_32") (pintype "bidirectional"))
    )
    (net (code "63") (name "unconnected-(IC1-VUSB-Pad41)") (class "Default")
      (node (ref "IC1") (pin "41") (pinfunction "VUSB_41") (pintype "bidirectional"))
    )
    (net (code "64") (name "unconnected-(IC2-NC-Pad2)") (class "Default")
      (node (ref "IC2") (pin "2") (pinfunction "NC_2") (pintype "bidirectional"))
    )
    (net (code "65") (name "unconnected-(IDC1-Pad3)") (class "Default")
      (node (ref "IDC1") (pin "3") (pinfunction "3_3") (pintype "passive"))
    )
    (net (code "66") (name "unconnected-(IDC1-Pad4)") (class "Default")
      (node (ref "IDC1") (pin "4") (pinfunction "4_4") (pintype "passive"))
    )
    (net (code "67") (name "unconnected-(IDC1-Pad5)") (class "Default")
      (node (ref "IDC1") (pin "5") (pinfunction "5_5") (pintype "passive"))
    )
    (net (code "68") (name "unconnected-(IDC1-Pad6)") (class "Default")
      (node (ref "IDC1") (pin "6") (pinfunction "6_6") (pintype "passive"))
    )
    (net (code "69") (name "unconnected-(IDC1-Pad7)") (class "Default")
      (node (ref "IDC1") (pin "7") (pinfunction "7_7") (pintype "passive"))
    )
    (net (code "70") (name "unconnected-(IDC1-Pad9)") (class "Default")
      (node (ref "IDC1") (pin "9") (pinfunction "9_9") (pintype "passive"))
    )
    (net (code "71") (name "unconnected-(IDC1-Pad10)") (class "Default")
      (node (ref "IDC1") (pin "10") (pinfunction "10_10") (pintype "passive"))
    )
    (net (code "72") (name "unconnected-(IDC1-Pad11)") (class "Default")
      (node (ref "IDC1") (pin "11") (pinfunction "11_11") (pintype "passive"))
    )
    (net (code "73") (name "unconnected-(IDC1-Pad13)") (class "Default")
      (node (ref "IDC1") (pin "13") (pinfunction "13_13") (pintype "passive"))
    )
    (net (code "74") (name "unconnected-(IDC1-Pad14)") (class "Default")
      (node (ref "IDC1") (pin "14") (pinfunction "14_14") (pintype "passive"))
    )
    (net (code "75") (name "unconnected-(IDC1-Pad15)") (class "Default")
      (node (ref "IDC1") (pin "15") (pinfunction "15_15") (pintype "passive"))
    )
    (net (code "76") (name "unconnected-(IDC1-Pad17)") (class "Default")
      (node (ref "IDC1") (pin "17") (pinfunction "17_17") (pintype "passive"))
    )
    (net (code "77") (name "unconnected-(IDC1-Pad19)") (class "Default")
      (node (ref "IDC1") (pin "19") (pinfunction "19_19") (pintype "passive"))
    )
    (net (code "78") (name "unconnected-(IDC1-Pad21)") (class "Default")
      (node (ref "IDC1") (pin "21") (pinfunction "21_21") (pintype "passive"))
    )
    (net (code "79") (name "unconnected-(IDC1-Pad23)") (class "Default")
      (node (ref "IDC1") (pin "23") (pinfunction "23_23") (pintype "passive"))
    )
    (net (code "80") (name "unconnected-(IDC1-Pad25)") (class "Default")
      (node (ref "IDC1") (pin "25") (pinfunction "25_25") (pintype "passive"))
    )
    (net (code "81") (name "unconnected-(IDC1-Pad27)") (class "Default")
      (node (ref "IDC1") (pin "27") (pinfunction "27_27") (pintype "passive"))
    )
    (net (code "82") (name "unconnected-(IDC1-Pad29)") (class "Default")
      (node (ref "IDC1") (pin "29") (pinfunction "29_29") (pintype "passive"))
    )
    (net (code "83") (name "unconnected-(IDC1-Pad31)") (class "Default")
      (node (ref "IDC1") (pin "31") (pinfunction "31_31") (pintype "passive"))
    )
    (net (code "84") (name "unconnected-(IDC1-Pad33)") (class "Default")
      (node (ref "IDC1") (pin "33") (pinfunction "33_33") (pintype "passive"))
    )
    (net (code "85") (name "unconnected-(J1-PadD+)") (class "Default")
      (node (ref "J1") (pin "D+") (pinfunction "D+_D+") (pintype "bidirectional"))
    )
    (net (code "86") (name "unconnected-(J1-PadD-)") (class "Default")
      (node (ref "J1") (pin "D-") (pinfunction "D-_D-") (pintype "bidirectional"))
    )
    (net (code "87") (name "unconnected-(SD1-DAT1-Pad8)") (class "Default")
      (node (ref "SD1") (pin "8") (pinfunction "DAT1_8") (pintype "bidirectional"))
    )
    (net (code "88") (name "unconnected-(SD1-DAT2-Pad9)") (class "Default")
      (node (ref "SD1") (pin "9") (pinfunction "DAT2_9") (pintype "bidirectional"))
    )
  )
)
